# DriverIC.net
KiCad netlist of a schematic drawn in Altium Designer
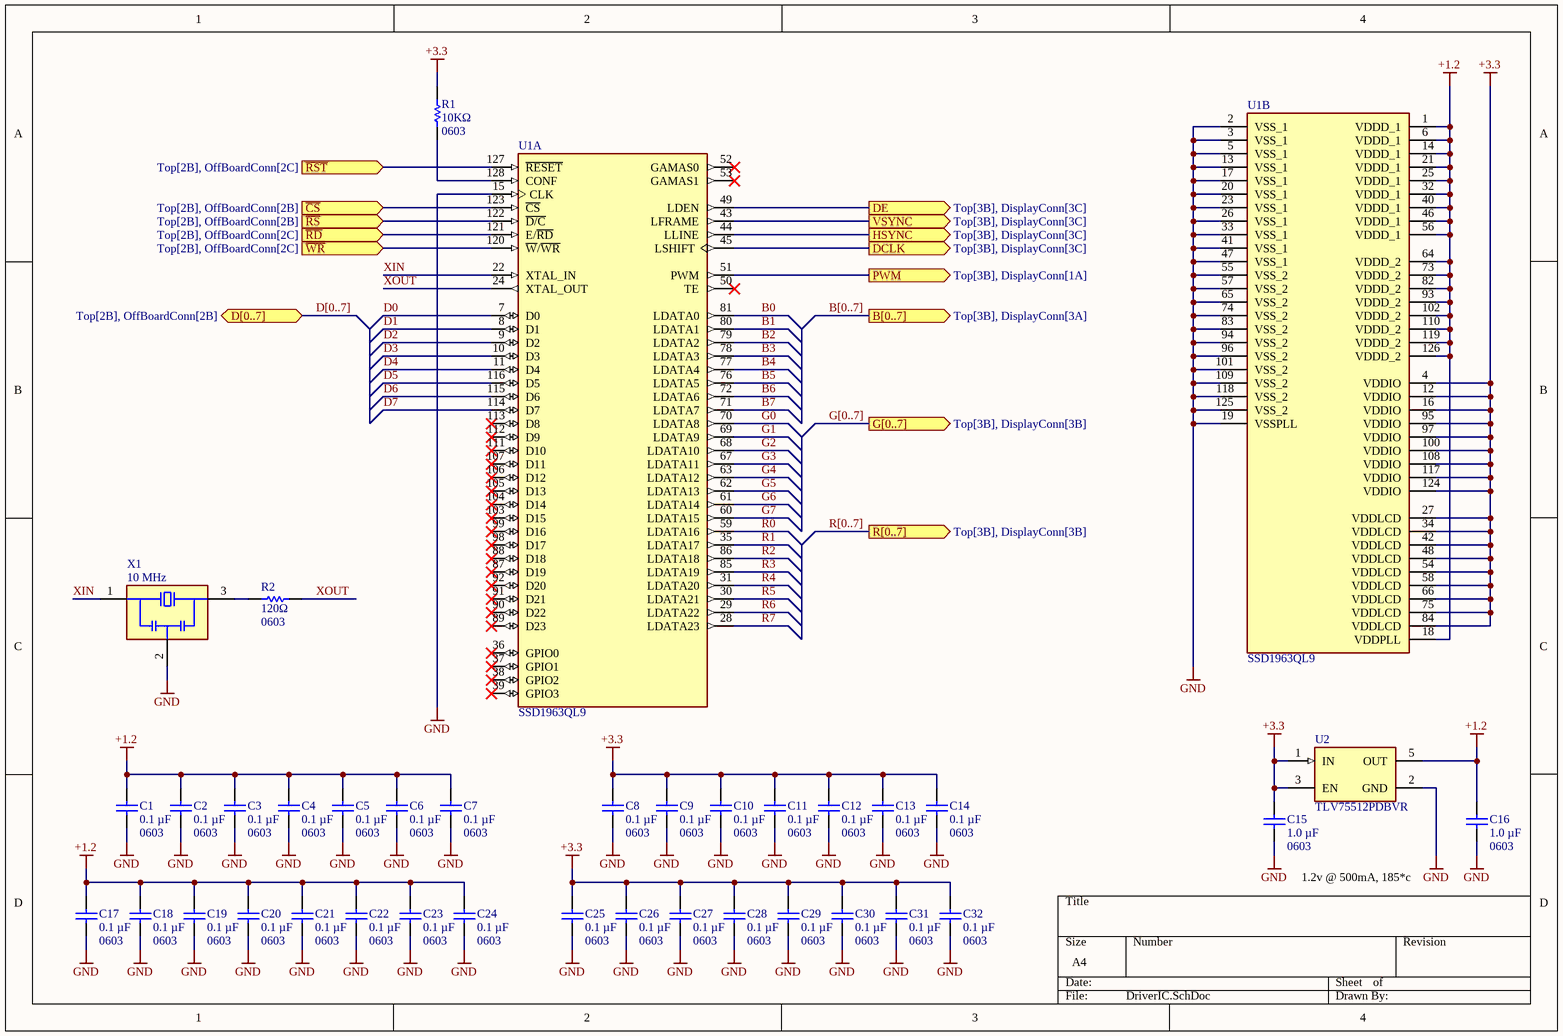
[diagram p0: DriverIC.SchDoc]

(export (version "E")
  (design (tool "Eeschema 10.0.6"))
  (components
    (comp (ref "C1")
      (value "0.1 µF")
      (footprint "0603")
      (description "0.1 µF ±20% 100V Ceramic Capacitor X7R 0603 (1608 Metric)")
      (fields (field (name "CASE") "0603") (field (name "TOLERANCE") "±20%") (field (name "VOLTAGE") "100V"))
      (libsource (lib "Murata Electronics") (part "GRM188R72A104MA35J"))
    )
    (comp (ref "C2")
      (value "0.1 µF")
      (footprint "0603")
      (description "0.1 µF ±20% 100V Ceramic Capacitor X7R 0603 (1608 Metric)")
      (fields (field (name "CASE") "0603") (field (name "TOLERANCE") "±20%") (field (name "VOLTAGE") "100V"))
      (libsource (lib "Murata Electronics") (part "GRM188R72A104MA35J"))
    )
    (comp (ref "C3")
      (value "0.1 µF")
      (footprint "0603")
      (description "0.1 µF ±20% 100V Ceramic Capacitor X7R 0603 (1608 Metric)")
      (fields (field (name "CASE") "0603") (field (name "TOLERANCE") "±20%") (field (name "VOLTAGE") "100V"))
      (libsource (lib "Murata Electronics") (part "GRM188R72A104MA35J"))
    )
    (comp (ref "C4")
      (value "0.1 µF")
      (footprint "0603")
      (description "0.1 µF ±20% 100V Ceramic Capacitor X7R 0603 (1608 Metric)")
      (fields (field (name "CASE") "0603") (field (name "TOLERANCE") "±20%") (field (name "VOLTAGE") "100V"))
      (libsource (lib "Murata Electronics") (part "GRM188R72A104MA35J"))
    )
    (comp (ref "C5")
      (value "0.1 µF")
      (footprint "0603")
      (description "0.1 µF ±20% 100V Ceramic Capacitor X7R 0603 (1608 Metric)")
      (fields (field (name "CASE") "0603") (field (name "TOLERANCE") "±20%") (field (name "VOLTAGE") "100V"))
      (libsource (lib "Murata Electronics") (part "GRM188R72A104MA35J"))
    )
    (comp (ref "C6")
      (value "0.1 µF")
      (footprint "0603")
      (description "0.1 µF ±20% 100V Ceramic Capacitor X7R 0603 (1608 Metric)")
      (fields (field (name "CASE") "0603") (field (name "TOLERANCE") "±20%") (field (name "VOLTAGE") "100V"))
      (libsource (lib "Murata Electronics") (part "GRM188R72A104MA35J"))
    )
    (comp (ref "C7")
      (value "0.1 µF")
      (footprint "0603")
      (description "0.1 µF ±20% 100V Ceramic Capacitor X7R 0603 (1608 Metric)")
      (fields (field (name "CASE") "0603") (field (name "TOLERANCE") "±20%") (field (name "VOLTAGE") "100V"))
      (libsource (lib "Murata Electronics") (part "GRM188R72A104MA35J"))
    )
    (comp (ref "C8")
      (value "0.1 µF")
      (footprint "0603")
      (description "0.1 µF ±20% 100V Ceramic Capacitor X7R 0603 (1608 Metric)")
      (fields (field (name "CASE") "0603") (field (name "TOLERANCE") "±20%") (field (name "VOLTAGE") "100V"))
      (libsource (lib "Murata Electronics") (part "GRM188R72A104MA35J"))
    )
    (comp (ref "C9")
      (value "0.1 µF")
      (footprint "0603")
      (description "0.1 µF ±20% 100V Ceramic Capacitor X7R 0603 (1608 Metric)")
      (fields (field (name "CASE") "0603") (field (name "TOLERANCE") "±20%") (field (name "VOLTAGE") "100V"))
      (libsource (lib "Murata Electronics") (part "GRM188R72A104MA35J"))
    )
    (comp (ref "C10")
      (value "0.1 µF")
      (footprint "0603")
      (description "0.1 µF ±20% 100V Ceramic Capacitor X7R 0603 (1608 Metric)")
      (fields (field (name "CASE") "0603") (field (name "TOLERANCE") "±20%") (field (name "VOLTAGE") "100V"))
      (libsource (lib "Murata Electronics") (part "GRM188R72A104MA35J"))
    )
    (comp (ref "C11")
      (value "0.1 µF")
      (footprint "0603")
      (description "0.1 µF ±20% 100V Ceramic Capacitor X7R 0603 (1608 Metric)")
      (fields (field (name "CASE") "0603") (field (name "TOLERANCE") "±20%") (field (name "VOLTAGE") "100V"))
      (libsource (lib "Murata Electronics") (part "GRM188R72A104MA35J"))
    )
    (comp (ref "C12")
      (value "0.1 µF")
      (footprint "0603")
      (description "0.1 µF ±20% 100V Ceramic Capacitor X7R 0603 (1608 Metric)")
      (fields (field (name "CASE") "0603") (field (name "TOLERANCE") "±20%") (field (name "VOLTAGE") "100V"))
      (libsource (lib "Murata Electronics") (part "GRM188R72A104MA35J"))
    )
    (comp (ref "C13")
      (value "0.1 µF")
      (footprint "0603")
      (description "0.1 µF ±20% 100V Ceramic Capacitor X7R 0603 (1608 Metric)")
      (fields (field (name "CASE") "0603") (field (name "TOLERANCE") "±20%") (field (name "VOLTAGE") "100V"))
      (libsource (lib "Murata Electronics") (part "GRM188R72A104MA35J"))
    )
    (comp (ref "C14")
      (value "0.1 µF")
      (footprint "0603")
      (description "0.1 µF ±20% 100V Ceramic Capacitor X7R 0603 (1608 Metric)")
      (fields (field (name "CASE") "0603") (field (name "TOLERANCE") "±20%") (field (name "VOLTAGE") "100V"))
      (libsource (lib "Murata Electronics") (part "GRM188R72A104MA35J"))
    )
    (comp (ref "C15")
      (value "1.0 µF")
      (footprint "0603")
      (description "1 µF ±10% 50V Ceramic Capacitor X7T 0603 (1608 Metric)")
      (fields (field (name "CASE") "0603") (field (name "TOLERANCE") "±10%") (field (name "VOLTAGE") "50V"))
      (libsource (lib "Murata Electronics") (part "GRM188D71H105KE01J"))
    )
    (comp (ref "C16")
      (value "1.0 µF")
      (footprint "0603")
      (description "1 µF ±10% 50V Ceramic Capacitor X7T 0603 (1608 Metric)")
      (fields (field (name "CASE") "0603") (field (name "TOLERANCE") "±10%") (field (name "VOLTAGE") "50V"))
      (libsource (lib "Murata Electronics") (part "GRM188D71H105KE01J"))
    )
    (comp (ref "C17")
      (value "0.1 µF")
      (footprint "0603")
      (description "0.1 µF ±20% 100V Ceramic Capacitor X7R 0603 (1608 Metric)")
      (fields (field (name "CASE") "0603") (field (name "TOLERANCE") "±20%") (field (name "VOLTAGE") "100V"))
      (libsource (lib "Murata Electronics") (part "GRM188R72A104MA35J"))
    )
    (comp (ref "C18")
      (value "0.1 µF")
      (footprint "0603")
      (description "0.1 µF ±20% 100V Ceramic Capacitor X7R 0603 (1608 Metric)")
      (fields (field (name "CASE") "0603") (field (name "TOLERANCE") "±20%") (field (name "VOLTAGE") "100V"))
      (libsource (lib "Murata Electronics") (part "GRM188R72A104MA35J"))
    )
    (comp (ref "C19")
      (value "0.1 µF")
      (footprint "0603")
      (description "0.1 µF ±20% 100V Ceramic Capacitor X7R 0603 (1608 Metric)")
      (fields (field (name "CASE") "0603") (field (name "TOLERANCE") "±20%") (field (name "VOLTAGE") "100V"))
      (libsource (lib "Murata Electronics") (part "GRM188R72A104MA35J"))
    )
    (comp (ref "C20")
      (value "0.1 µF")
      (footprint "0603")
      (description "0.1 µF ±20% 100V Ceramic Capacitor X7R 0603 (1608 Metric)")
      (fields (field (name "CASE") "0603") (field (name "TOLERANCE") "±20%") (field (name "VOLTAGE") "100V"))
      (libsource (lib "Murata Electronics") (part "GRM188R72A104MA35J"))
    )
    (comp (ref "C21")
      (value "0.1 µF")
      (footprint "0603")
      (description "0.1 µF ±20% 100V Ceramic Capacitor X7R 0603 (1608 Metric)")
      (fields (field (name "CASE") "0603") (field (name "TOLERANCE") "±20%") (field (name "VOLTAGE") "100V"))
      (libsource (lib "Murata Electronics") (part "GRM188R72A104MA35J"))
    )
    (comp (ref "C22")
      (value "0.1 µF")
      (footprint "0603")
      (description "0.1 µF ±20% 100V Ceramic Capacitor X7R 0603 (1608 Metric)")
      (fields (field (name "CASE") "0603") (field (name "TOLERANCE") "±20%") (field (name "VOLTAGE") "100V"))
      (libsource (lib "Murata Electronics") (part "GRM188R72A104MA35J"))
    )
    (comp (ref "C23")
      (value "0.1 µF")
      (footprint "0603")
      (description "0.1 µF ±20% 100V Ceramic Capacitor X7R 0603 (1608 Metric)")
      (fields (field (name "CASE") "0603") (field (name "TOLERANCE") "±20%") (field (name "VOLTAGE") "100V"))
      (libsource (lib "Murata Electronics") (part "GRM188R72A104MA35J"))
    )
    (comp (ref "C24")
      (value "0.1 µF")
      (footprint "0603")
      (description "0.1 µF ±20% 100V Ceramic Capacitor X7R 0603 (1608 Metric)")
      (fields (field (name "CASE") "0603") (field (name "TOLERANCE") "±20%") (field (name "VOLTAGE") "100V"))
      (libsource (lib "Murata Electronics") (part "GRM188R72A104MA35J"))
    )
    (comp (ref "C25")
      (value "0.1 µF")
      (footprint "0603")
      (description "0.1 µF ±20% 100V Ceramic Capacitor X7R 0603 (1608 Metric)")
      (fields (field (name "CASE") "0603") (field (name "TOLERANCE") "±20%") (field (name "VOLTAGE") "100V"))
      (libsource (lib "Murata Electronics") (part "GRM188R72A104MA35J"))
    )
    (comp (ref "C26")
      (value "0.1 µF")
      (footprint "0603")
      (description "0.1 µF ±20% 100V Ceramic Capacitor X7R 0603 (1608 Metric)")
      (fields (field (name "CASE") "0603") (field (name "TOLERANCE") "±20%") (field (name "VOLTAGE") "100V"))
      (libsource (lib "Murata Electronics") (part "GRM188R72A104MA35J"))
    )
    (comp (ref "C27")
      (value "0.1 µF")
      (footprint "0603")
      (description "0.1 µF ±20% 100V Ceramic Capacitor X7R 0603 (1608 Metric)")
      (fields (field (name "CASE") "0603") (field (name "TOLERANCE") "±20%") (field (name "VOLTAGE") "100V"))
      (libsource (lib "Murata Electronics") (part "GRM188R72A104MA35J"))
    )
    (comp (ref "C28")
      (value "0.1 µF")
      (footprint "0603")
      (description "0.1 µF ±20% 100V Ceramic Capacitor X7R 0603 (1608 Metric)")
      (fields (field (name "CASE") "0603") (field (name "TOLERANCE") "±20%") (field (name "VOLTAGE") "100V"))
      (libsource (lib "Murata Electronics") (part "GRM188R72A104MA35J"))
    )
    (comp (ref "C29")
      (value "0.1 µF")
      (footprint "0603")
      (description "0.1 µF ±20% 100V Ceramic Capacitor X7R 0603 (1608 Metric)")
      (fields (field (name "CASE") "0603") (field (name "TOLERANCE") "±20%") (field (name "VOLTAGE") "100V"))
      (libsource (lib "Murata Electronics") (part "GRM188R72A104MA35J"))
    )
    (comp (ref "C30")
      (value "0.1 µF")
      (footprint "0603")
      (description "0.1 µF ±20% 100V Ceramic Capacitor X7R 0603 (1608 Metric)")
      (fields (field (name "CASE") "0603") (field (name "TOLERANCE") "±20%") (field (name "VOLTAGE") "100V"))
      (libsource (lib "Murata Electronics") (part "GRM188R72A104MA35J"))
    )
    (comp (ref "C31")
      (value "0.1 µF")
      (footprint "0603")
      (description "0.1 µF ±20% 100V Ceramic Capacitor X7R 0603 (1608 Metric)")
      (fields (field (name "CASE") "0603") (field (name "TOLERANCE") "±20%") (field (name "VOLTAGE") "100V"))
      (libsource (lib "Murata Electronics") (part "GRM188R72A104MA35J"))
    )
    (comp (ref "C32")
      (value "0.1 µF")
      (footprint "0603")
      (description "0.1 µF ±20% 100V Ceramic Capacitor X7R 0603 (1608 Metric)")
      (fields (field (name "CASE") "0603") (field (name "TOLERANCE") "±20%") (field (name "VOLTAGE") "100V"))
      (libsource (lib "Murata Electronics") (part "GRM188R72A104MA35J"))
    )
    (comp (ref "R1")
      (value "10KΩ")
      (footprint "0603")
      (description "10 kOhms ±1% 0.1W, 1/10W Chip Resistor 0603 (1608 Metric) Automotive AEC-Q200 Thick Film")
      (fields (field (name "CASE") "0603") (field (name "TOLERANCE") "1%") (field (name "POWER") "0.1W"))
      (libsource (lib "Stackpole Electronics Inc") (part "RMCF0603FG10K0"))
    )
    (comp (ref "R2")
      (value "120Ω")
      (footprint "0603")
      (description "120 Ohms ±1% 0.1W, 1/10W Chip Resistor 0603 (1608 Metric) Automotive AEC-Q200 Thick Film")
      (fields (field (name "CASE") "0603") (field (name "TOLERANCE") "1%") (field (name "POWER") "0.1W"))
      (libsource (lib "Stackpole Electronics Inc") (part "RMCF0603FT120R"))
    )
    (comp (ref "U1")
      (value "SSD1963QL9")
      (footprint "PCBComponent_1")
      (description "LQFP-128(14x14) LCD Drivers ROHS")
      (libsource (lib "Solomon Systech") (part "SSD1963QL9"))
    )
    (comp (ref "U2")
      (value "TLV75512PDBVR")
      (footprint "SOT-23-5")
      (description "Linear Voltage Regulator IC Positive Fixed 1 Output 500mA SOT-23-5")
      (libsource (lib "Texas Instruments") (part "TLV75512PDBVR"))
    )
    (comp (ref "X1")
      (value "10 MHz")
      (footprint "3-SMD")
      (description "10 MHz Ceramic Resonator Built in Capacitor 33 pF ±0.2% 40 Ohms -40°C ~ 85°C Surface Mount")
      (fields (field (name "Comment") "CSTNE10M0G550000R0"))
      (libsource (lib "Murata Electronics") (part "CSTNE10M0G550000R0"))
    )
  )
  (nets
    (net (code "1") (name "+1.2") (class "Default")
      (node (ref "C1") (pin "2") (pinfunction "2_2") (pintype "passive"))
      (node (ref "C16") (pin "1") (pinfunction "1_1") (pintype "passive"))
      (node (ref "C17") (pin "2") (pinfunction "2_2") (pintype "passive"))
      (node (ref "C18") (pin "2") (pinfunction "2_2") (pintype "passive"))
      (node (ref "C19") (pin "2") (pinfunction "2_2") (pintype "passive"))
      (node (ref "C2") (pin "2") (pinfunction "2_2") (pintype "passive"))
      (node (ref "C20") (pin "2") (pinfunction "2_2") (pintype "passive"))
      (node (ref "C21") (pin "2") (pinfunction "2_2") (pintype "passive"))
      (node (ref "C22") (pin "2") (pinfunction "2_2") (pintype "passive"))
      (node (ref "C23") (pin "2") (pinfunction "2_2") (pintype "passive"))
      (node (ref "C24") (pin "2") (pinfunction "2_2") (pintype "passive"))
      (node (ref "C3") (pin "2") (pinfunction "2_2") (pintype "passive"))
      (node (ref "C4") (pin "2") (pinfunction "2_2") (pintype "passive"))
      (node (ref "C5") (pin "2") (pinfunction "2_2") (pintype "passive"))
      (node (ref "C6") (pin "2") (pinfunction "2_2") (pintype "passive"))
      (node (ref "C7") (pin "2") (pinfunction "2_2") (pintype "passive"))
      (node (ref "U1") (pin "1") (pinfunction "VDDD_1_1") (pintype "power_in"))
      (node (ref "U1") (pin "102") (pinfunction "VDDD_2_102") (pintype "power_in"))
      (node (ref "U1") (pin "110") (pinfunction "VDDD_2_110") (pintype "power_in"))
      (node (ref "U1") (pin "119") (pinfunction "VDDD_2_119") (pintype "power_in"))
      (node (ref "U1") (pin "126") (pinfunction "VDDD_2_126") (pintype "power_in"))
      (node (ref "U1") (pin "14") (pinfunction "VDDD_1_14") (pintype "power_in"))
      (node (ref "U1") (pin "18") (pinfunction "VDDPLL_18") (pintype "power_in"))
      (node (ref "U1") (pin "21") (pinfunction "VDDD_1_21") (pintype "power_in"))
      (node (ref "U1") (pin "25") (pinfunction "VDDD_1_25") (pintype "power_in"))
      (node (ref "U1") (pin "32") (pinfunction "VDDD_1_32") (pintype "power_in"))
      (node (ref "U1") (pin "40") (pinfunction "VDDD_1_40") (pintype "power_in"))
      (node (ref "U1") (pin "46") (pinfunction "VDDD_1_46") (pintype "power_in"))
      (node (ref "U1") (pin "56") (pinfunction "VDDD_1_56") (pintype "power_in"))
      (node (ref "U1") (pin "6") (pinfunction "VDDD_1_6") (pintype "power_in"))
      (node (ref "U1") (pin "64") (pinfunction "VDDD_2_64") (pintype "power_in"))
      (node (ref "U1") (pin "73") (pinfunction "VDDD_2_73") (pintype "power_in"))
      (node (ref "U1") (pin "82") (pinfunction "VDDD_2_82") (pintype "power_in"))
      (node (ref "U1") (pin "93") (pinfunction "VDDD_2_93") (pintype "power_in"))
      (node (ref "U2") (pin "5") (pinfunction "OUT_5") (pintype "passive"))
    )
    (net (code "2") (name "+3.3") (class "Default")
      (node (ref "C10") (pin "2") (pinfunction "2_2") (pintype "passive"))
      (node (ref "C11") (pin "2") (pinfunction "2_2") (pintype "passive"))
      (node (ref "C12") (pin "2") (pinfunction "2_2") (pintype "passive"))
      (node (ref "C13") (pin "2") (pinfunction "2_2") (pintype "passive"))
      (node (ref "C14") (pin "2") (pinfunction "2_2") (pintype "passive"))
      (node (ref "C15") (pin "1") (pinfunction "1_1") (pintype "passive"))
      (node (ref "C25") (pin "2") (pinfunction "2_2") (pintype "passive"))
      (node (ref "C26") (pin "2") (pinfunction "2_2") (pintype "passive"))
      (node (ref "C27") (pin "2") (pinfunction "2_2") (pintype "passive"))
      (node (ref "C28") (pin "2") (pinfunction "2_2") (pintype "passive"))
      (node (ref "C29") (pin "2") (pinfunction "2_2") (pintype "passive"))
      (node (ref "C30") (pin "2") (pinfunction "2_2") (pintype "passive"))
      (node (ref "C31") (pin "2") (pinfunction "2_2") (pintype "passive"))
      (node (ref "C32") (pin "2") (pinfunction "2_2") (pintype "passive"))
      (node (ref "C8") (pin "2") (pinfunction "2_2") (pintype "passive"))
      (node (ref "C9") (pin "2") (pinfunction "2_2") (pintype "passive"))
      (node (ref "R1") (pin "1") (pinfunction "1_1") (pintype "passive"))
      (node (ref "U1") (pin "100") (pinfunction "VDDIO_100") (pintype "power_in"))
      (node (ref "U1") (pin "108") (pinfunction "VDDIO_108") (pintype "power_in"))
      (node (ref "U1") (pin "117") (pinfunction "VDDIO_117") (pintype "power_in"))
      (node (ref "U1") (pin "12") (pinfunction "VDDIO_12") (pintype "power_in"))
      (node (ref "U1") (pin "124") (pinfunction "VDDIO_124") (pintype "power_in"))
      (node (ref "U1") (pin "16") (pinfunction "VDDIO_16") (pintype "power_in"))
      (node (ref "U1") (pin "27") (pinfunction "VDDLCD_27") (pintype "power_in"))
      (node (ref "U1") (pin "34") (pinfunction "VDDLCD_34") (pintype "power_in"))
      (node (ref "U1") (pin "4") (pinfunction "VDDIO_4") (pintype "power_in"))
      (node (ref "U1") (pin "42") (pinfunction "VDDLCD_42") (pintype "power_in"))
      (node (ref "U1") (pin "48") (pinfunction "VDDLCD_48") (pintype "power_in"))
      (node (ref "U1") (pin "54") (pinfunction "VDDLCD_54") (pintype "power_in"))
      (node (ref "U1") (pin "58") (pinfunction "VDDLCD_58") (pintype "power_in"))
      (node (ref "U1") (pin "66") (pinfunction "VDDLCD_66") (pintype "power_in"))
      (node (ref "U1") (pin "75") (pinfunction "VDDLCD_75") (pintype "power_in"))
      (node (ref "U1") (pin "84") (pinfunction "VDDLCD_84") (pintype "power_in"))
      (node (ref "U1") (pin "95") (pinfunction "VDDIO_95") (pintype "power_in"))
      (node (ref "U1") (pin "97") (pinfunction "VDDIO_97") (pintype "power_in"))
      (node (ref "U2") (pin "1") (pinfunction "IN_1") (pintype "input"))
      (node (ref "U2") (pin "3") (pinfunction "EN_3") (pintype "passive"))
    )
    (net (code "3") (name "/B0") (class "Default")
      (node (ref "U1") (pin "81") (pinfunction "LDATA0_81") (pintype "output"))
    )
    (net (code "4") (name "/B1") (class "Default")
      (node (ref "U1") (pin "80") (pinfunction "LDATA1_80") (pintype "output"))
    )
    (net (code "5") (name "/B2") (class "Default")
      (node (ref "U1") (pin "79") (pinfunction "LDATA2_79") (pintype "output"))
    )
    (net (code "6") (name "/B3") (class "Default")
      (node (ref "U1") (pin "78") (pinfunction "LDATA3_78") (pintype "output"))
    )
    (net (code "7") (name "/B4") (class "Default")
      (node (ref "U1") (pin "77") (pinfunction "LDATA4_77") (pintype "output"))
    )
    (net (code "8") (name "/B5") (class "Default")
      (node (ref "U1") (pin "76") (pinfunction "LDATA5_76") (pintype "output"))
    )
    (net (code "9") (name "/B6") (class "Default")
      (node (ref "U1") (pin "72") (pinfunction "LDATA6_72") (pintype "output"))
    )
    (net (code "10") (name "/B7") (class "Default")
      (node (ref "U1") (pin "71") (pinfunction "LDATA7_71") (pintype "output"))
    )
    (net (code "12") (name "/D0") (class "Default")
      (node (ref "U1") (pin "7") (pinfunction "D0_7") (pintype "bidirectional"))
    )
    (net (code "13") (name "/D1") (class "Default")
      (node (ref "U1") (pin "8") (pinfunction "D1_8") (pintype "bidirectional"))
    )
    (net (code "14") (name "/D2") (class "Default")
      (node (ref "U1") (pin "9") (pinfunction "D2_9") (pintype "bidirectional"))
    )
    (net (code "15") (name "/D3") (class "Default")
      (node (ref "U1") (pin "10") (pinfunction "D3_10") (pintype "bidirectional"))
    )
    (net (code "16") (name "/D4") (class "Default")
      (node (ref "U1") (pin "11") (pinfunction "D4_11") (pintype "bidirectional"))
    )
    (net (code "17") (name "/D5") (class "Default")
      (node (ref "U1") (pin "116") (pinfunction "D5_116") (pintype "bidirectional"))
    )
    (net (code "18") (name "/D6") (class "Default")
      (node (ref "U1") (pin "115") (pinfunction "D6_115") (pintype "bidirectional"))
    )
    (net (code "19") (name "/D7") (class "Default")
      (node (ref "U1") (pin "114") (pinfunction "D7_114") (pintype "bidirectional"))
    )
    (net (code "20") (name "/DCLK") (class "Default")
      (node (ref "U1") (pin "45") (pinfunction "LSHIFT_45") (pintype "output"))
    )
    (net (code "21") (name "/DE") (class "Default")
      (node (ref "U1") (pin "49") (pinfunction "LDEN_49") (pintype "output"))
    )
    (net (code "23") (name "/G0") (class "Default")
      (node (ref "U1") (pin "70") (pinfunction "LDATA8_70") (pintype "output"))
    )
    (net (code "24") (name "/G1") (class "Default")
      (node (ref "U1") (pin "69") (pinfunction "LDATA9_69") (pintype "output"))
    )
    (net (code "25") (name "/G2") (class "Default")
      (node (ref "U1") (pin "68") (pinfunction "LDATA10_68") (pintype "output"))
    )
    (net (code "26") (name "/G3") (class "Default")
      (node (ref "U1") (pin "67") (pinfunction "LDATA11_67") (pintype "output"))
    )
    (net (code "27") (name "/G4") (class "Default")
      (node (ref "U1") (pin "63") (pinfunction "LDATA12_63") (pintype "output"))
    )
    (net (code "28") (name "/G5") (class "Default")
      (node (ref "U1") (pin "62") (pinfunction "LDATA13_62") (pintype "output"))
    )
    (net (code "29") (name "/G6") (class "Default")
      (node (ref "U1") (pin "61") (pinfunction "LDATA14_61") (pintype "output"))
    )
    (net (code "30") (name "/G7") (class "Default")
      (node (ref "U1") (pin "60") (pinfunction "LDATA15_60") (pintype "output"))
    )
    (net (code "32") (name "/HSYNC") (class "Default")
      (node (ref "U1") (pin "44") (pinfunction "LLINE_44") (pintype "output"))
    )
    (net (code "33") (name "/PWM") (class "Default")
      (node (ref "U1") (pin "51") (pinfunction "PWM_51") (pintype "output"))
    )
    (net (code "34") (name "/R0") (class "Default")
      (node (ref "U1") (pin "59") (pinfunction "LDATA16_59") (pintype "output"))
    )
    (net (code "35") (name "/R1") (class "Default")
      (node (ref "U1") (pin "35") (pinfunction "LDATA17_35") (pintype "output"))
    )
    (net (code "36") (name "/R2") (class "Default")
      (node (ref "U1") (pin "86") (pinfunction "LDATA18_86") (pintype "output"))
    )
    (net (code "37") (name "/R3") (class "Default")
      (node (ref "U1") (pin "85") (pinfunction "LDATA19_85") (pintype "output"))
    )
    (net (code "38") (name "/R4") (class "Default")
      (node (ref "U1") (pin "31") (pinfunction "LDATA20_31") (pintype "output"))
    )
    (net (code "39") (name "/R5") (class "Default")
      (node (ref "U1") (pin "30") (pinfunction "LDATA21_30") (pintype "output"))
    )
    (net (code "40") (name "/R6") (class "Default")
      (node (ref "U1") (pin "29") (pinfunction "LDATA22_29") (pintype "output"))
    )
    (net (code "41") (name "/R7") (class "Default")
      (node (ref "U1") (pin "28") (pinfunction "LDATA23_28") (pintype "output"))
    )
    (net (code "43") (name "/VSYNC") (class "Default")
      (node (ref "U1") (pin "43") (pinfunction "LFRAME_43") (pintype "output"))
    )
    (net (code "44") (name "/XIN") (class "Default")
      (node (ref "U1") (pin "22") (pinfunction "XTAL_IN_22") (pintype "input"))
      (node (ref "X1") (pin "1") (pinfunction "IN_1") (pintype "passive"))
    )
    (net (code "45") (name "/XOUT") (class "Default")
      (node (ref "R2") (pin "1") (pinfunction "1_1") (pintype "passive"))
      (node (ref "U1") (pin "24") (pinfunction "XTAL_OUT_24") (pintype "output"))
    )
    (net (code "46") (name "/~{CS}") (class "Default")
      (node (ref "U1") (pin "123") (pinfunction "~{CS}_123") (pintype "input"))
    )
    (net (code "47") (name "/~{RD}") (class "Default")
      (node (ref "U1") (pin "121") (pinfunction "E/~{RD}_121") (pintype "input"))
    )
    (net (code "48") (name "/~{RST}") (class "Default")
      (node (ref "U1") (pin "127") (pinfunction "~{RESET}_127") (pintype "input"))
    )
    (net (code "49") (name "/~{RS}") (class "Default")
      (node (ref "U1") (pin "122") (pinfunction "~{D/C}_122") (pintype "input"))
    )
    (net (code "50") (name "/~{WR}") (class "Default")
      (node (ref "U1") (pin "120") (pinfunction "~{W}/~{WR}_120") (pintype "input"))
    )
    (net (code "51") (name "GND") (class "Default")
      (node (ref "C1") (pin "1") (pinfunction "1_1") (pintype "passive"))
      (node (ref "C10") (pin "1") (pinfunction "1_1") (pintype "passive"))
      (node (ref "C11") (pin "1") (pinfunction "1_1") (pintype "passive"))
      (node (ref "C12") (pin "1") (pinfunction "1_1") (pintype "passive"))
      (node (ref "C13") (pin "1") (pinfunction "1_1") (pintype "passive"))
      (node (ref "C14") (pin "1") (pinfunction "1_1") (pintype "passive"))
      (node (ref "C15") (pin "2") (pinfunction "2_2") (pintype "passive"))
      (node (ref "C16") (pin "2") (pinfunction "2_2") (pintype "passive"))
      (node (ref "C17") (pin "1") (pinfunction "1_1") (pintype "passive"))
      (node (ref "C18") (pin "1") (pinfunction "1_1") (pintype "passive"))
      (node (ref "C19") (pin "1") (pinfunction "1_1") (pintype "passive"))
      (node (ref "C2") (pin "1") (pinfunction "1_1") (pintype "passive"))
      (node (ref "C20") (pin "1") (pinfunction "1_1") (pintype "passive"))
      (node (ref "C21") (pin "1") (pinfunction "1_1") (pintype "passive"))
      (node (ref "C22") (pin "1") (pinfunction "1_1") (pintype "passive"))
      (node (ref "C23") (pin "1") (pinfunction "1_1") (pintype "passive"))
      (node (ref "C24") (pin "1") (pinfunction "1_1") (pintype "passive"))
      (node (ref "C25") (pin "1") (pinfunction "1_1") (pintype "passive"))
      (node (ref "C26") (pin "1") (pinfunction "1_1") (pintype "passive"))
      (node (ref "C27") (pin "1") (pinfunction "1_1") (pintype "passive"))
      (node (ref "C28") (pin "1") (pinfunction "1_1") (pintype "passive"))
      (node (ref "C29") (pin "1") (pinfunction "1_1") (pintype "passive"))
      (node (ref "C3") (pin "1") (pinfunction "1_1") (pintype "passive"))
      (node (ref "C30") (pin "1") (pinfunction "1_1") (pintype "passive"))
      (node (ref "C31") (pin "1") (pinfunction "1_1") (pintype "passive"))
      (node (ref "C32") (pin "1") (pinfunction "1_1") (pintype "passive"))
      (node (ref "C4") (pin "1") (pinfunction "1_1") (pintype "passive"))
      (node (ref "C5") (pin "1") (pinfunction "1_1") (pintype "passive"))
      (node (ref "C6") (pin "1") (pinfunction "1_1") (pintype "passive"))
      (node (ref "C7") (pin "1") (pinfunction "1_1") (pintype "passive"))
      (node (ref "C8") (pin "1") (pinfunction "1_1") (pintype "passive"))
      (node (ref "C9") (pin "1") (pinfunction "1_1") (pintype "passive"))
      (node (ref "U1") (pin "101") (pinfunction "VSS_2_101") (pintype "power_in"))
      (node (ref "U1") (pin "109") (pinfunction "VSS_2_109") (pintype "power_in"))
      (node (ref "U1") (pin "118") (pinfunction "VSS_2_118") (pintype "power_in"))
      (node (ref "U1") (pin "125") (pinfunction "VSS_2_125") (pintype "power_in"))
      (node (ref "U1") (pin "13") (pinfunction "VSS_1_13") (pintype "power_in"))
      (node (ref "U1") (pin "15") (pinfunction "CLK_15") (pintype "input"))
      (node (ref "U1") (pin "17") (pinfunction "VSS_1_17") (pintype "power_in"))
      (node (ref "U1") (pin "19") (pinfunction "VSSPLL_19") (pintype "power_in"))
      (node (ref "U1") (pin "2") (pinfunction "VSS_1_2") (pintype "power_in"))
      (node (ref "U1") (pin "20") (pinfunction "VSS_1_20") (pintype "power_in"))
      (node (ref "U1") (pin "23") (pinfunction "VSS_1_23") (pintype "power_in"))
      (node (ref "U1") (pin "26") (pinfunction "VSS_1_26") (pintype "power_in"))
      (node (ref "U1") (pin "3") (pinfunction "VSS_1_3") (pintype "power_in"))
      (node (ref "U1") (pin "33") (pinfunction "VSS_1_33") (pintype "power_in"))
      (node (ref "U1") (pin "41") (pinfunction "VSS_1_41") (pintype "power_in"))
      (node (ref "U1") (pin "47") (pinfunction "VSS_1_47") (pintype "power_in"))
      (node (ref "U1") (pin "5") (pinfunction "VSS_1_5") (pintype "power_in"))
      (node (ref "U1") (pin "55") (pinfunction "VSS_2_55") (pintype "power_in"))
      (node (ref "U1") (pin "57") (pinfunction "VSS_2_57") (pintype "power_in"))
      (node (ref "U1") (pin "65") (pinfunction "VSS_2_65") (pintype "power_in"))
      (node (ref "U1") (pin "74") (pinfunction "VSS_2_74") (pintype "power_in"))
      (node (ref "U1") (pin "83") (pinfunction "VSS_2_83") (pintype "power_in"))
      (node (ref "U1") (pin "94") (pinfunction "VSS_2_94") (pintype "power_in"))
      (node (ref "U1") (pin "96") (pinfunction "VSS_2_96") (pintype "power_in"))
      (node (ref "U2") (pin "2") (pinfunction "GND_2") (pintype "power_in"))
      (node (ref "X1") (pin "2") (pinfunction "GND_2") (pintype "power_in"))
    )
    (net (code "52") (name "Net-(U1A-CONF)") (class "Default")
      (node (ref "R1") (pin "2") (pinfunction "2_2") (pintype "passive"))
      (node (ref "U1") (pin "128") (pinfunction "CONF_128") (pintype "input"))
    )
    (net (code "53") (name "Net-(X1-OUT)") (class "Default")
      (node (ref "R2") (pin "2") (pinfunction "2_2") (pintype "passive"))
      (node (ref "X1") (pin "3") (pinfunction "OUT_3") (pintype "passive"))
    )
    (net (code "54") (name "unconnected-(U1A-D8-Pad113)") (class "Default")
      (node (ref "U1") (pin "113") (pinfunction "D8_113") (pintype "bidirectional+no_connect"))
    )
    (net (code "55") (name "unconnected-(U1A-D9-Pad112)") (class "Default")
      (node (ref "U1") (pin "112") (pinfunction "D9_112") (pintype "bidirectional+no_connect"))
    )
    (net (code "56") (name "unconnected-(U1A-D10-Pad111)") (class "Default")
      (node (ref "U1") (pin "111") (pinfunction "D10_111") (pintype "bidirectional+no_connect"))
    )
    (net (code "57") (name "unconnected-(U1A-D11-Pad107)") (class "Default")
      (node (ref "U1") (pin "107") (pinfunction "D11_107") (pintype "bidirectional+no_connect"))
    )
    (net (code "58") (name "unconnected-(U1A-D12-Pad106)") (class "Default")
      (node (ref "U1") (pin "106") (pinfunction "D12_106") (pintype "bidirectional+no_connect"))
    )
    (net (code "59") (name "unconnected-(U1A-D13-Pad105)") (class "Default")
      (node (ref "U1") (pin "105") (pinfunction "D13_105") (pintype "bidirectional+no_connect"))
    )
    (net (code "60") (name "unconnected-(U1A-D14-Pad104)") (class "Default")
      (node (ref "U1") (pin "104") (pinfunction "D14_104") (pintype "bidirectional+no_connect"))
    )
    (net (code "61") (name "unconnected-(U1A-D15-Pad103)") (class "Default")
      (node (ref "U1") (pin "103") (pinfunction "D15_103") (pintype "bidirectional+no_connect"))
    )
    (net (code "62") (name "unconnected-(U1A-D16-Pad99)") (class "Default")
      (node (ref "U1") (pin "99") (pinfunction "D16_99") (pintype "bidirectional+no_connect"))
    )
    (net (code "63") (name "unconnected-(U1A-D17-Pad98)") (class "Default")
      (node (ref "U1") (pin "98") (pinfunction "D17_98") (pintype "bidirectional+no_connect"))
    )
    (net (code "64") (name "unconnected-(U1A-D18-Pad88)") (class "Default")
      (node (ref "U1") (pin "88") (pinfunction "D18_88") (pintype "bidirectional+no_connect"))
    )
    (net (code "65") (name "unconnected-(U1A-D19-Pad87)") (class "Default")
      (node (ref "U1") (pin "87") (pinfunction "D19_87") (pintype "bidirectional+no_connect"))
    )
    (net (code "66") (name "unconnected-(U1A-D20-Pad92)") (class "Default")
      (node (ref "U1") (pin "92") (pinfunction "D20_92") (pintype "bidirectional+no_connect"))
    )
    (net (code "67") (name "unconnected-(U1A-D21-Pad91)") (class "Default")
      (node (ref "U1") (pin "91") (pinfunction "D21_91") (pintype "bidirectional+no_connect"))
    )
    (net (code "68") (name "unconnected-(U1A-D22-Pad90)") (class "Default")
      (node (ref "U1") (pin "90") (pinfunction "D22_90") (pintype "bidirectional+no_connect"))
    )
    (net (code "69") (name "unconnected-(U1A-D23-Pad89)") (class "Default")
      (node (ref "U1") (pin "89") (pinfunction "D23_89") (pintype "bidirectional+no_connect"))
    )
    (net (code "70") (name "unconnected-(U1A-GAMAS0-Pad52)") (class "Default")
      (node (ref "U1") (pin "52") (pinfunction "GAMAS0_52") (pintype "output+no_connect"))
    )
    (net (code "71") (name "unconnected-(U1A-GAMAS1-Pad53)") (class "Default")
      (node (ref "U1") (pin "53") (pinfunction "GAMAS1_53") (pintype "output+no_connect"))
    )
    (net (code "72") (name "unconnected-(U1A-GPIO0-Pad36)") (class "Default")
      (node (ref "U1") (pin "36") (pinfunction "GPIO0_36") (pintype "bidirectional+no_connect"))
    )
    (net (code "73") (name "unconnected-(U1A-GPIO1-Pad37)") (class "Default")
      (node (ref "U1") (pin "37") (pinfunction "GPIO1_37") (pintype "bidirectional+no_connect"))
    )
    (net (code "74") (name "unconnected-(U1A-GPIO2-Pad38)") (class "Default")
      (node (ref "U1") (pin "38") (pinfunction "GPIO2_38") (pintype "bidirectional+no_connect"))
    )
    (net (code "75") (name "unconnected-(U1A-GPIO3-Pad39)") (class "Default")
      (node (ref "U1") (pin "39") (pinfunction "GPIO3_39") (pintype "bidirectional+no_connect"))
    )
    (net (code "76") (name "unconnected-(U1A-TE-Pad50)") (class "Default")
      (node (ref "U1") (pin "50") (pinfunction "TE_50") (pintype "output+no_connect"))
    )
  )
)
